# tip_dirver.net
KiCad netlist of a schematic drawn in Altium Designer
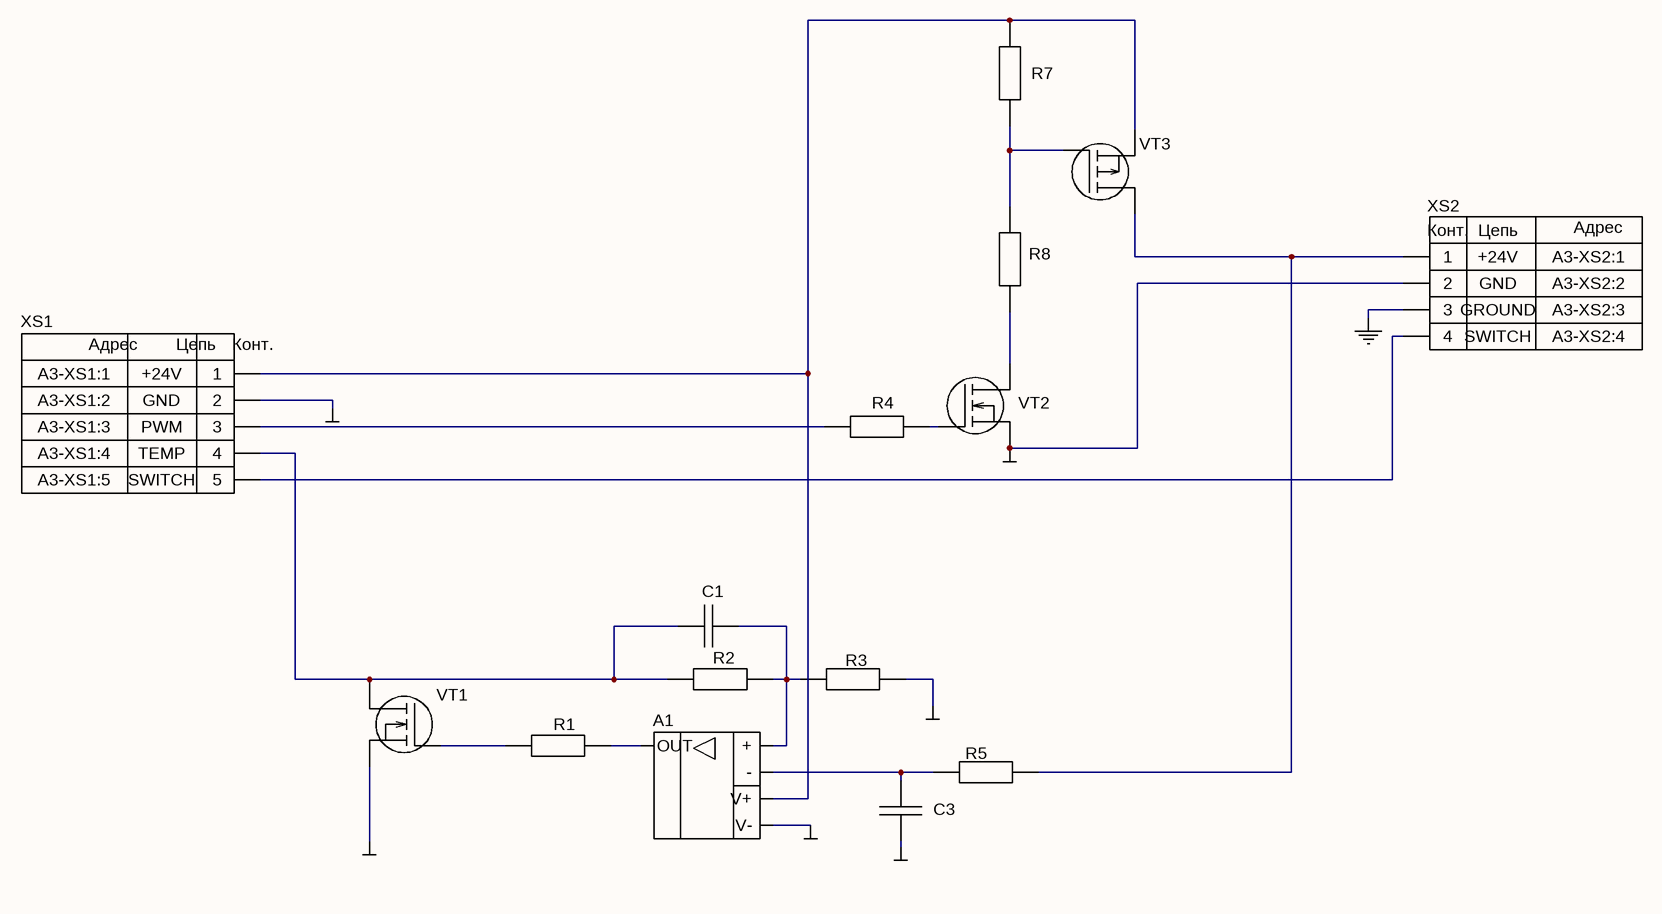
[diagram p0: tip_dirver.SchDoc]

(export (version "E")
  (design (tool "Eeschema 10.0.6"))
  (components
    (comp (ref "A1")
      (value "LMV321ILT")
      (footprint "SOT23-5")
      (libsource (lib "elems") (part "single_channel_op_amp"))
    )
    (comp (ref "C1") (value "100 нФ") (footprint "CAP: 0603") (libsource (lib "elems") (part "C_const")))
    (comp (ref "C3") (value "100 нФ") (footprint "CAP: 0603") (libsource (lib "elems") (part "C_const")))
    (comp (ref "R1") (value "Res") (footprint "RES: 0603") (libsource (lib "elems") (part "Res")))
    (comp (ref "R2") (value "Res") (footprint "RES: 0603") (libsource (lib "elems") (part "Res")))
    (comp (ref "R3") (value "Res") (footprint "RES: 0603") (libsource (lib "elems") (part "Res")))
    (comp (ref "R4") (value "Res") (footprint "RES: 0603") (libsource (lib "elems") (part "Res")))
    (comp (ref "R5") (value "Res") (footprint "RES: 0603") (libsource (lib "elems") (part "Res")))
    (comp (ref "R7") (value "Res") (footprint "RES: 1206") (libsource (lib "elems") (part "Res")))
    (comp (ref "R8") (value "Res") (footprint "RES: 1206") (libsource (lib "elems") (part "Res")))
    (comp (ref "VT1") (value "FDV303N") (footprint "SOT23") (libsource (lib "elems") (part "n-mosfet")))
    (comp (ref "VT2") (value "FDV303N") (footprint "SOT23") (libsource (lib "elems") (part "n-mosfet")))
    (comp (ref "VT3") (value "p-mosfet") (footprint "DPAK") (libsource (lib "elems") (part "p-mosfet")))
    (comp (ref "XS1")
      (value "X5")
      (footprint "CON: CWF-5")
      (fields
        (field (name "CIRTUIT5") "SWITCH")
        (field (name "CIRCUIT4") "TEMP")
        (field (name "CIRCUIT3") "PWM")
        (field (name "CIRCUIT2") "GND")
        (field (name "CIRCUIT1") "+24V")
        (field (name "=ADDRESS5") "A3-XS1:5")
        (field (name "=ADDRESS4") "A3-XS1:4")
        (field (name "=ADDRESS3") "A3-XS1:3")
        (field (name "=ADDRESS2") "A3-XS1:2")
        (field (name "=ADDRESS1") "A3-XS1:1")
      )
      (libsource (lib "elems") (part "X5"))
    )
    (comp (ref "XS2")
      (value "X4")
      (footprint "HDR1X4")
      (fields
        (field (name "CIRCUIT2") "GND")
        (field (name "CIRCUIT3") "GROUND")
        (field (name "CIRCUIT1") "+24V")
        (field (name "CIRCUIT4") "SWITCH")
        (field (name "=ADDRESS4") "A3-XS2:4")
        (field (name "=ADDRESS3") "A3-XS2:3")
        (field (name "=ADDRESS2") "A3-XS2:2")
        (field (name "=ADDRESS1") "A3-XS2:1")
      )
      (libsource (lib "elems") (part "X4"))
    )
  )
  (nets
    (net (code "1") (name "GND") (class "Default")
      (node (ref "A1") (pin "2") (pinfunction "V-_2") (pintype "passive"))
      (node (ref "C3") (pin "1") (pinfunction "1_1") (pintype "passive"))
      (node (ref "R3") (pin "2") (pinfunction "6_2") (pintype "passive"))
      (node (ref "VT1") (pin "3") (pinfunction "3_3") (pintype "passive"))
      (node (ref "VT2") (pin "3") (pinfunction "3_3") (pintype "passive"))
      (node (ref "XS1") (pin "2") (pinfunction "2_2") (pintype "passive"))
      (node (ref "XS2") (pin "2") (pinfunction "2_2") (pintype "passive"))
    )
    (net (code "2") (name "GROUND") (class "Default")
      (node (ref "XS2") (pin "3") (pinfunction "3_3") (pintype "passive"))
    )
    (net (code "3") (name "Net-(A1-+)") (class "Default")
      (node (ref "A1") (pin "1") (pinfunction "+_1") (pintype "passive"))
      (node (ref "C1") (pin "1") (pinfunction "1_1") (pintype "passive"))
      (node (ref "R2") (pin "2") (pinfunction "6_2") (pintype "passive"))
      (node (ref "R3") (pin "1") (pinfunction "1_1") (pintype "passive"))
    )
    (net (code "4") (name "Net-(A1--)") (class "Default")
      (node (ref "A1") (pin "3") (pinfunction "-_3") (pintype "passive"))
      (node (ref "C3") (pin "2") (pinfunction "2_2") (pintype "passive"))
      (node (ref "R5") (pin "1") (pinfunction "1_1") (pintype "passive"))
    )
    (net (code "5") (name "Net-(A1-OUT)") (class "Default")
      (node (ref "A1") (pin "4") (pinfunction "OUT_4") (pintype "passive"))
      (node (ref "R1") (pin "2") (pinfunction "6_2") (pintype "passive"))
    )
    (net (code "6") (name "Net-(A1-V+)") (class "Default")
      (node (ref "A1") (pin "5") (pinfunction "V+_5") (pintype "passive"))
      (node (ref "R7") (pin "2") (pinfunction "6_2") (pintype "passive"))
      (node (ref "VT3") (pin "3") (pinfunction "3_3") (pintype "passive"))
      (node (ref "XS1") (pin "1") (pinfunction "1_1") (pintype "passive"))
    )
    (net (code "7") (name "Net-(C1-Pad2)") (class "Default")
      (node (ref "C1") (pin "2") (pinfunction "2_2") (pintype "passive"))
      (node (ref "R2") (pin "1") (pinfunction "1_1") (pintype "passive"))
      (node (ref "VT1") (pin "2") (pinfunction "2_2") (pintype "passive"))
      (node (ref "XS1") (pin "4") (pinfunction "4_4") (pintype "passive"))
    )
    (net (code "8") (name "Net-(R1-Pad1)") (class "Default")
      (node (ref "R1") (pin "1") (pinfunction "1_1") (pintype "passive"))
      (node (ref "VT1") (pin "1") (pinfunction "1_1") (pintype "passive"))
    )
    (net (code "9") (name "Net-(R4-6)") (class "Default")
      (node (ref "R4") (pin "2") (pinfunction "6_2") (pintype "passive"))
      (node (ref "VT2") (pin "1") (pinfunction "1_1") (pintype "passive"))
    )
    (net (code "10") (name "Net-(R4-Pad1)") (class "Default")
      (node (ref "R4") (pin "1") (pinfunction "1_1") (pintype "passive"))
      (node (ref "XS1") (pin "3") (pinfunction "3_3") (pintype "passive"))
    )
    (net (code "11") (name "Net-(R5-6)") (class "Default")
      (node (ref "R5") (pin "2") (pinfunction "6_2") (pintype "passive"))
      (node (ref "VT3") (pin "2") (pinfunction "2_2") (pintype "passive"))
      (node (ref "XS2") (pin "1") (pinfunction "1_1") (pintype "passive"))
    )
    (net (code "12") (name "Net-(R8-6)") (class "Default")
      (node (ref "R7") (pin "1") (pinfunction "1_1") (pintype "passive"))
      (node (ref "R8") (pin "2") (pinfunction "6_2") (pintype "passive"))
      (node (ref "VT3") (pin "1") (pinfunction "1_1") (pintype "passive"))
    )
    (net (code "13") (name "Net-(R8-Pad1)") (class "Default")
      (node (ref "R8") (pin "1") (pinfunction "1_1") (pintype "passive"))
      (node (ref "VT2") (pin "2") (pinfunction "2_2") (pintype "passive"))
    )
    (net (code "14") (name "Net-(XS1-Pad5)") (class "Default")
      (node (ref "XS1") (pin "5") (pinfunction "5_5") (pintype "passive"))
      (node (ref "XS2") (pin "4") (pinfunction "4_4") (pintype "passive"))
    )
  )
)
